# fc.net
KiCad netlist of a schematic drawn in EAGLE
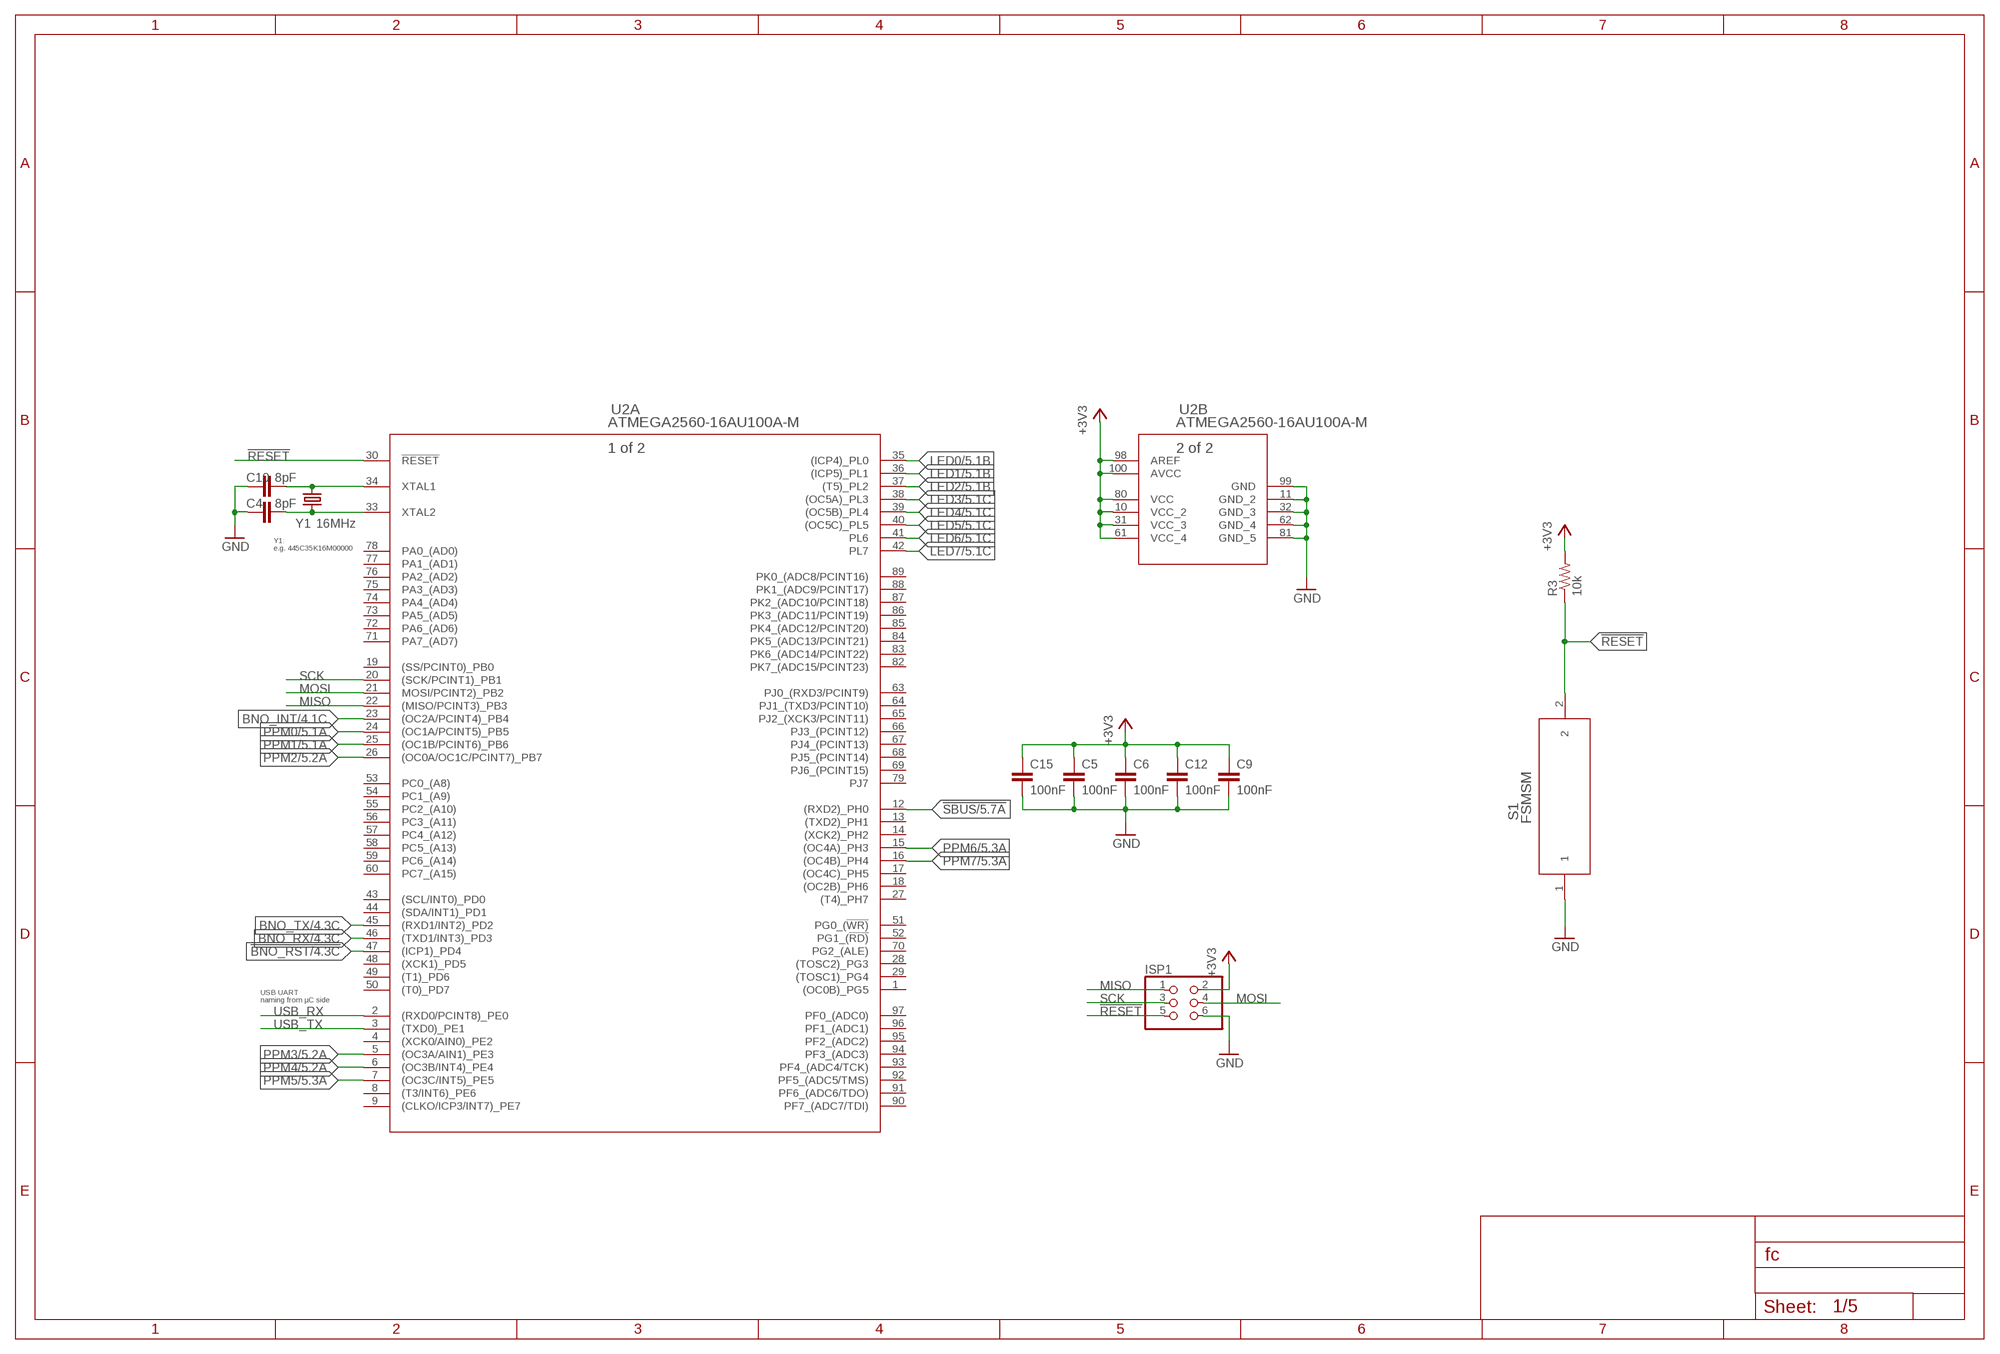
[diagram p0: schematic, sheet 1]
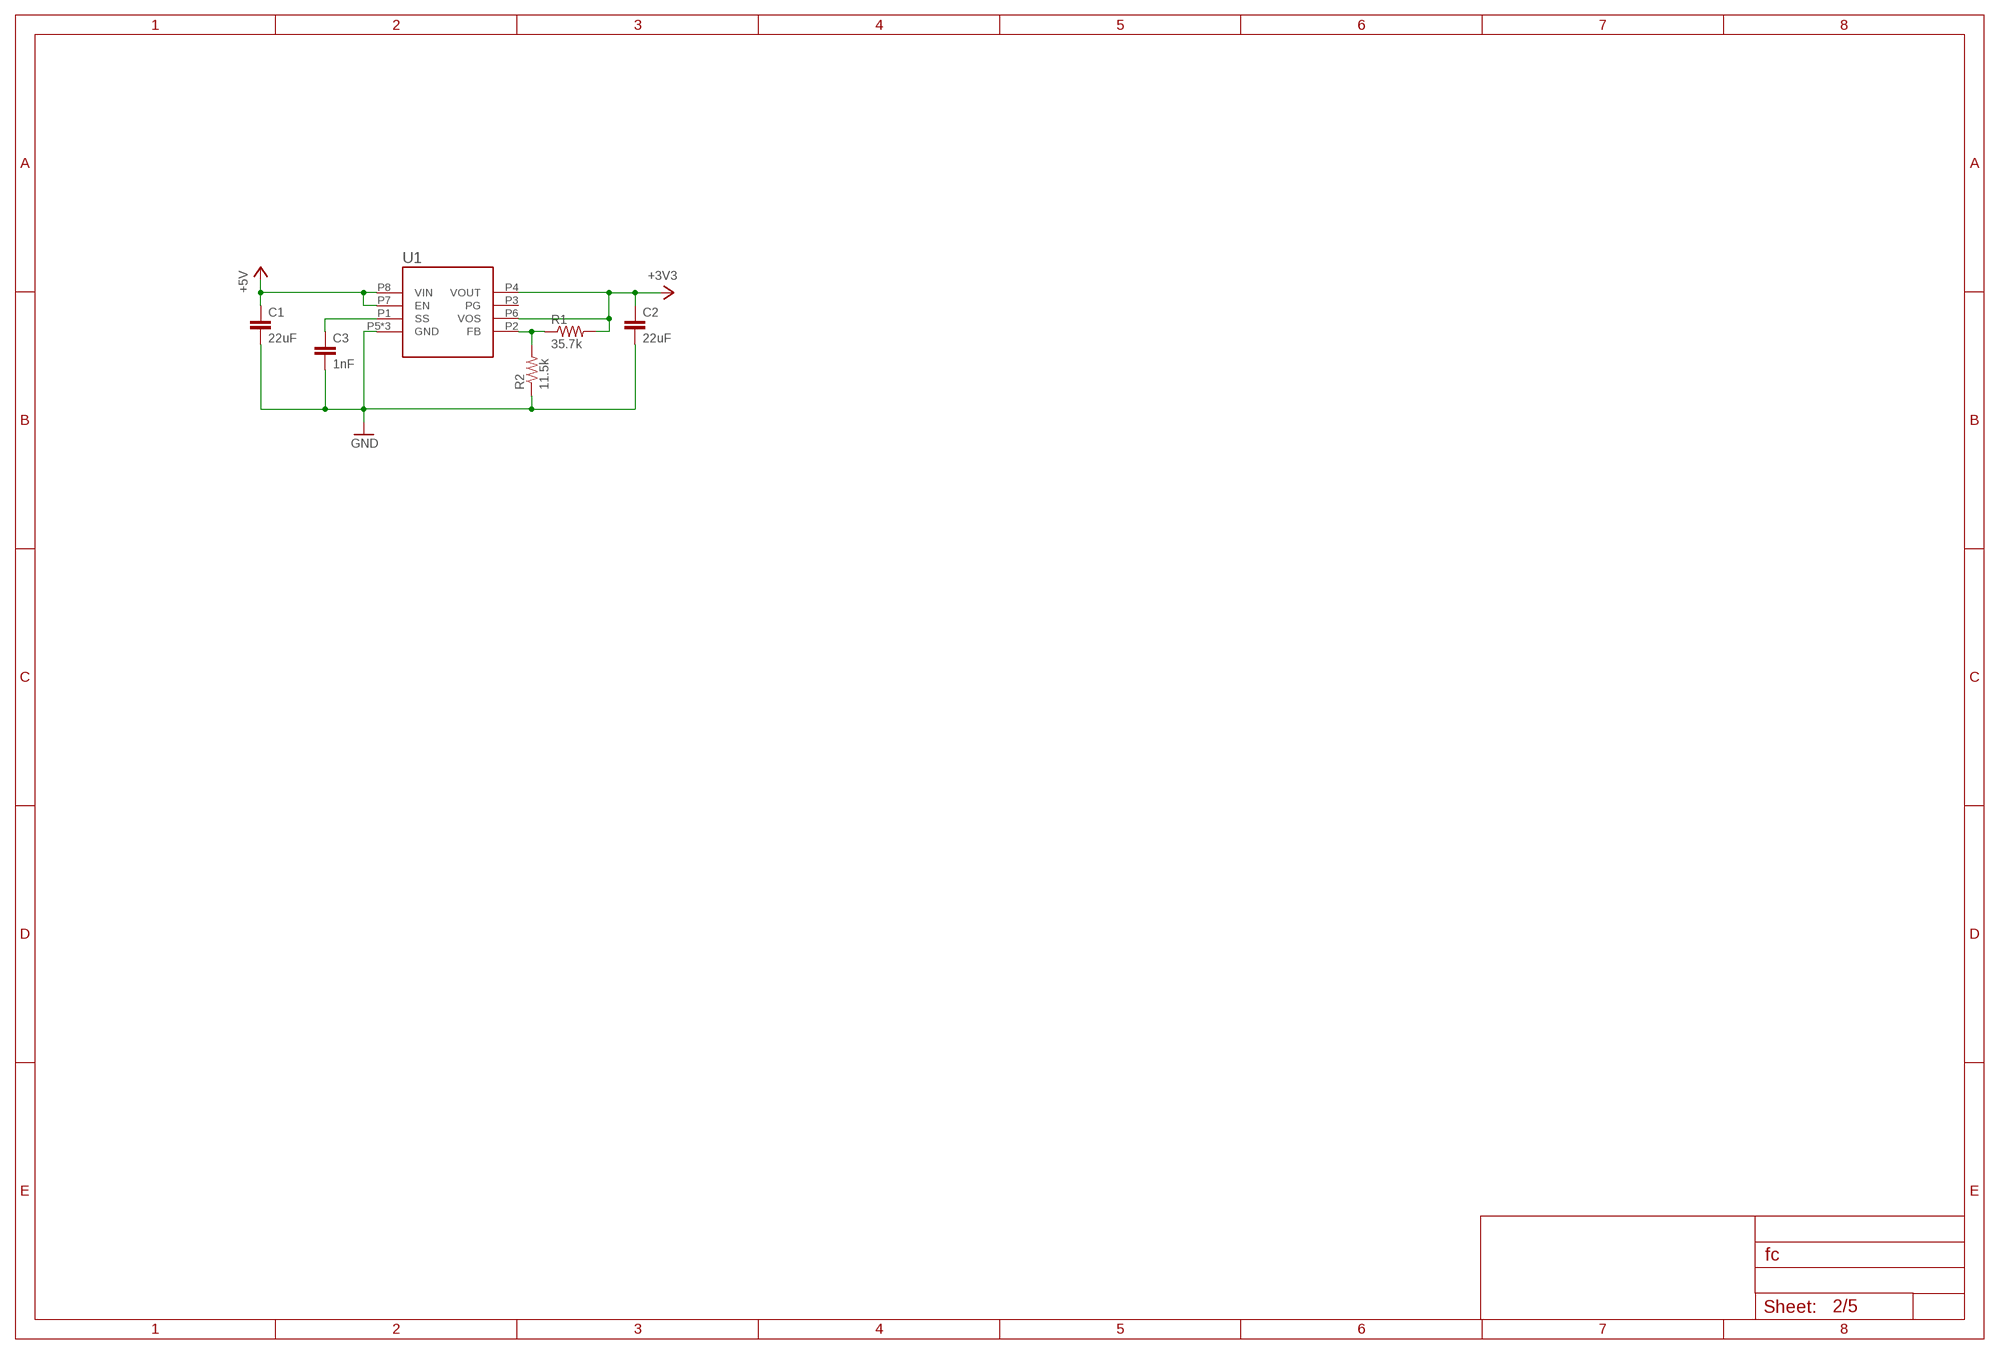
[diagram p1: schematic, sheet 2]
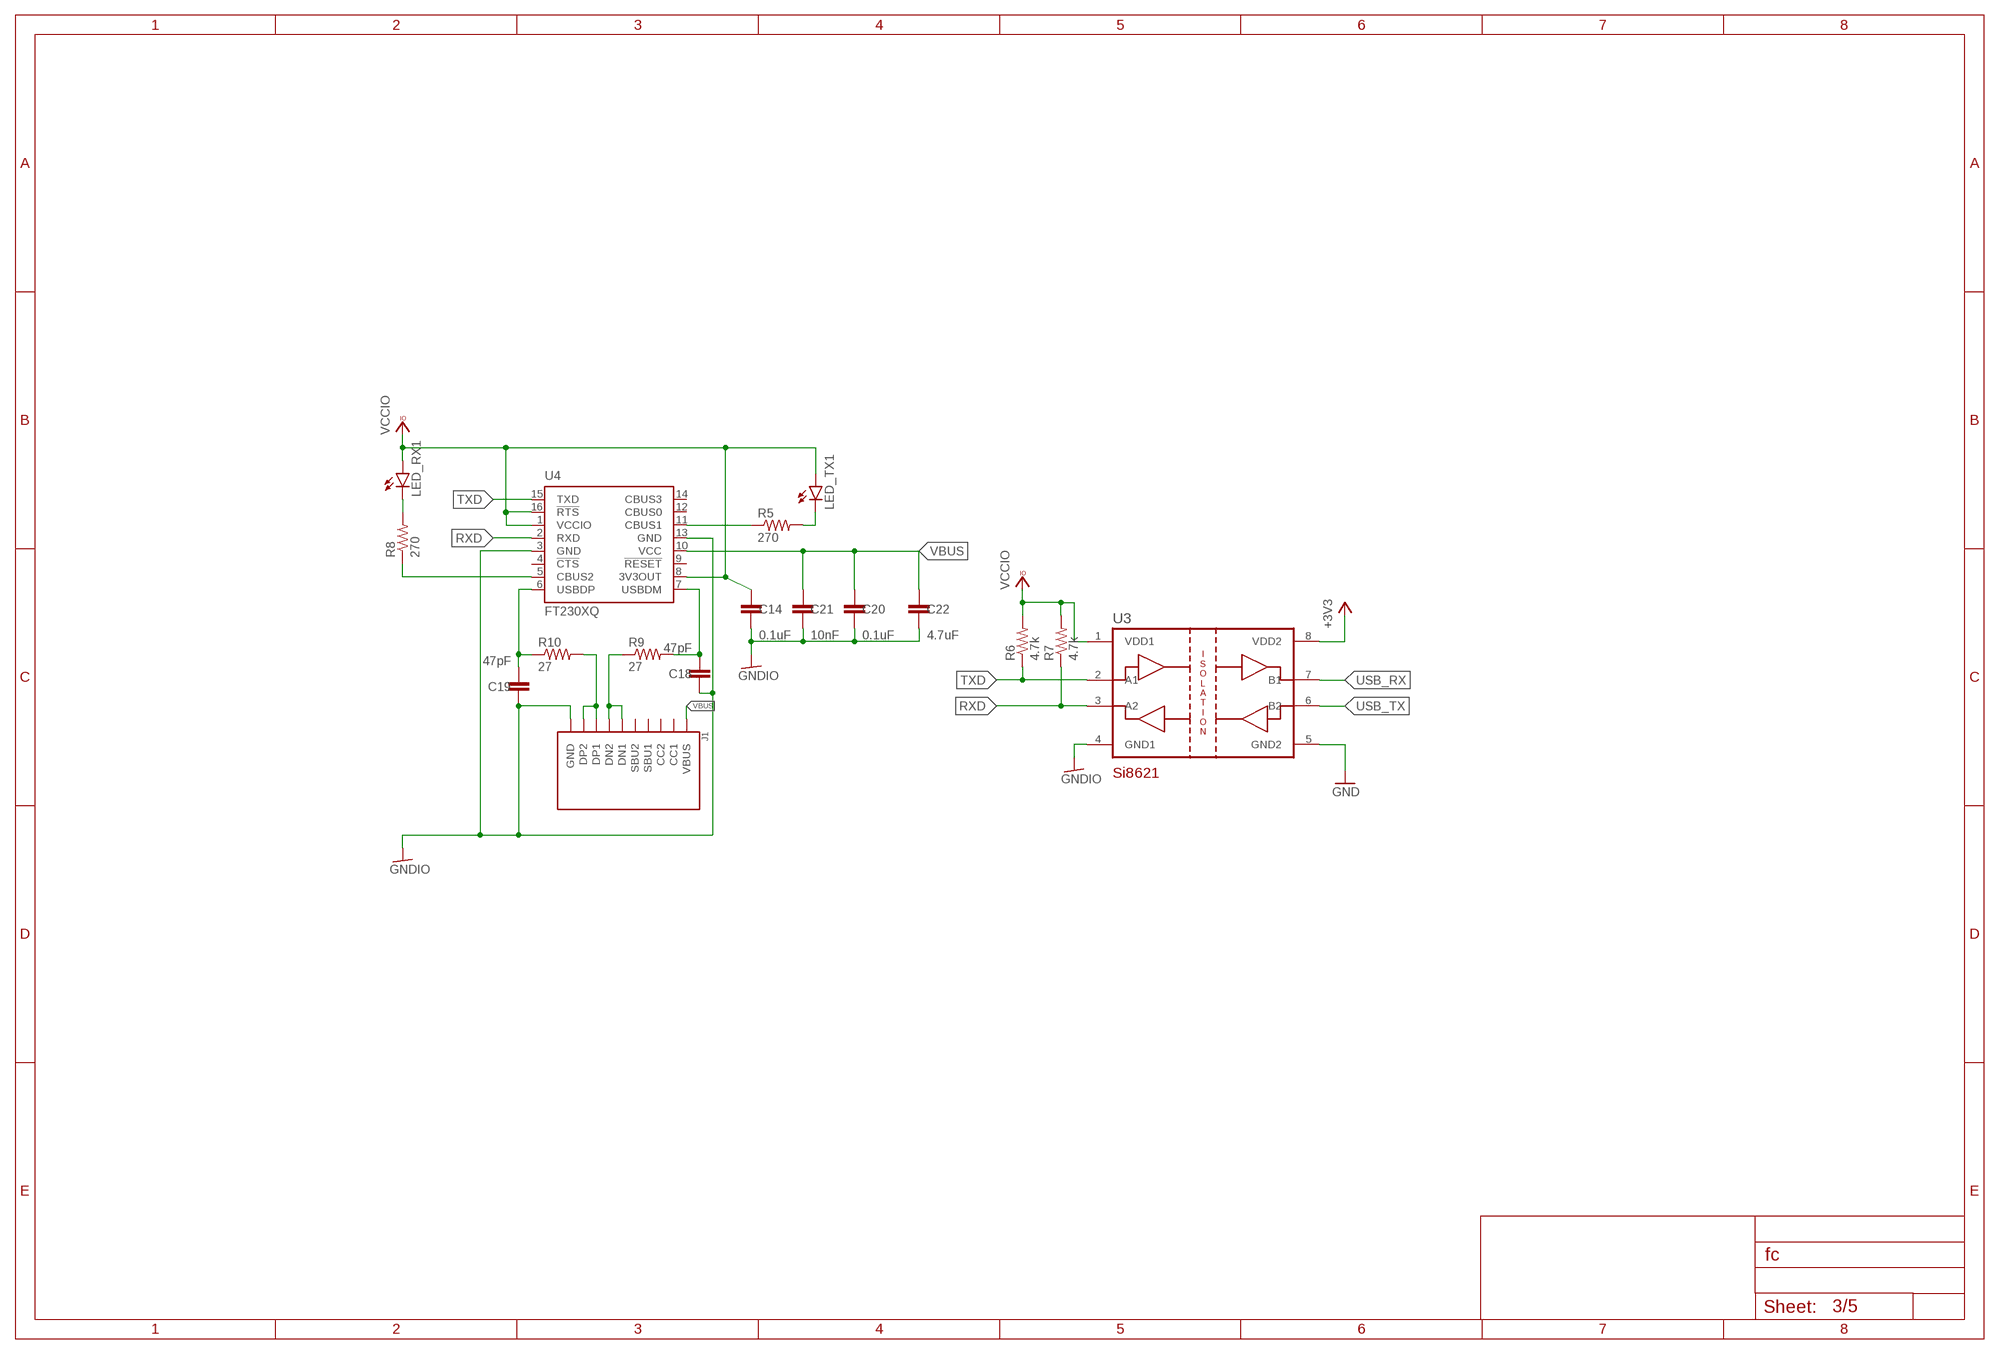
[diagram p2: schematic, sheet 3]
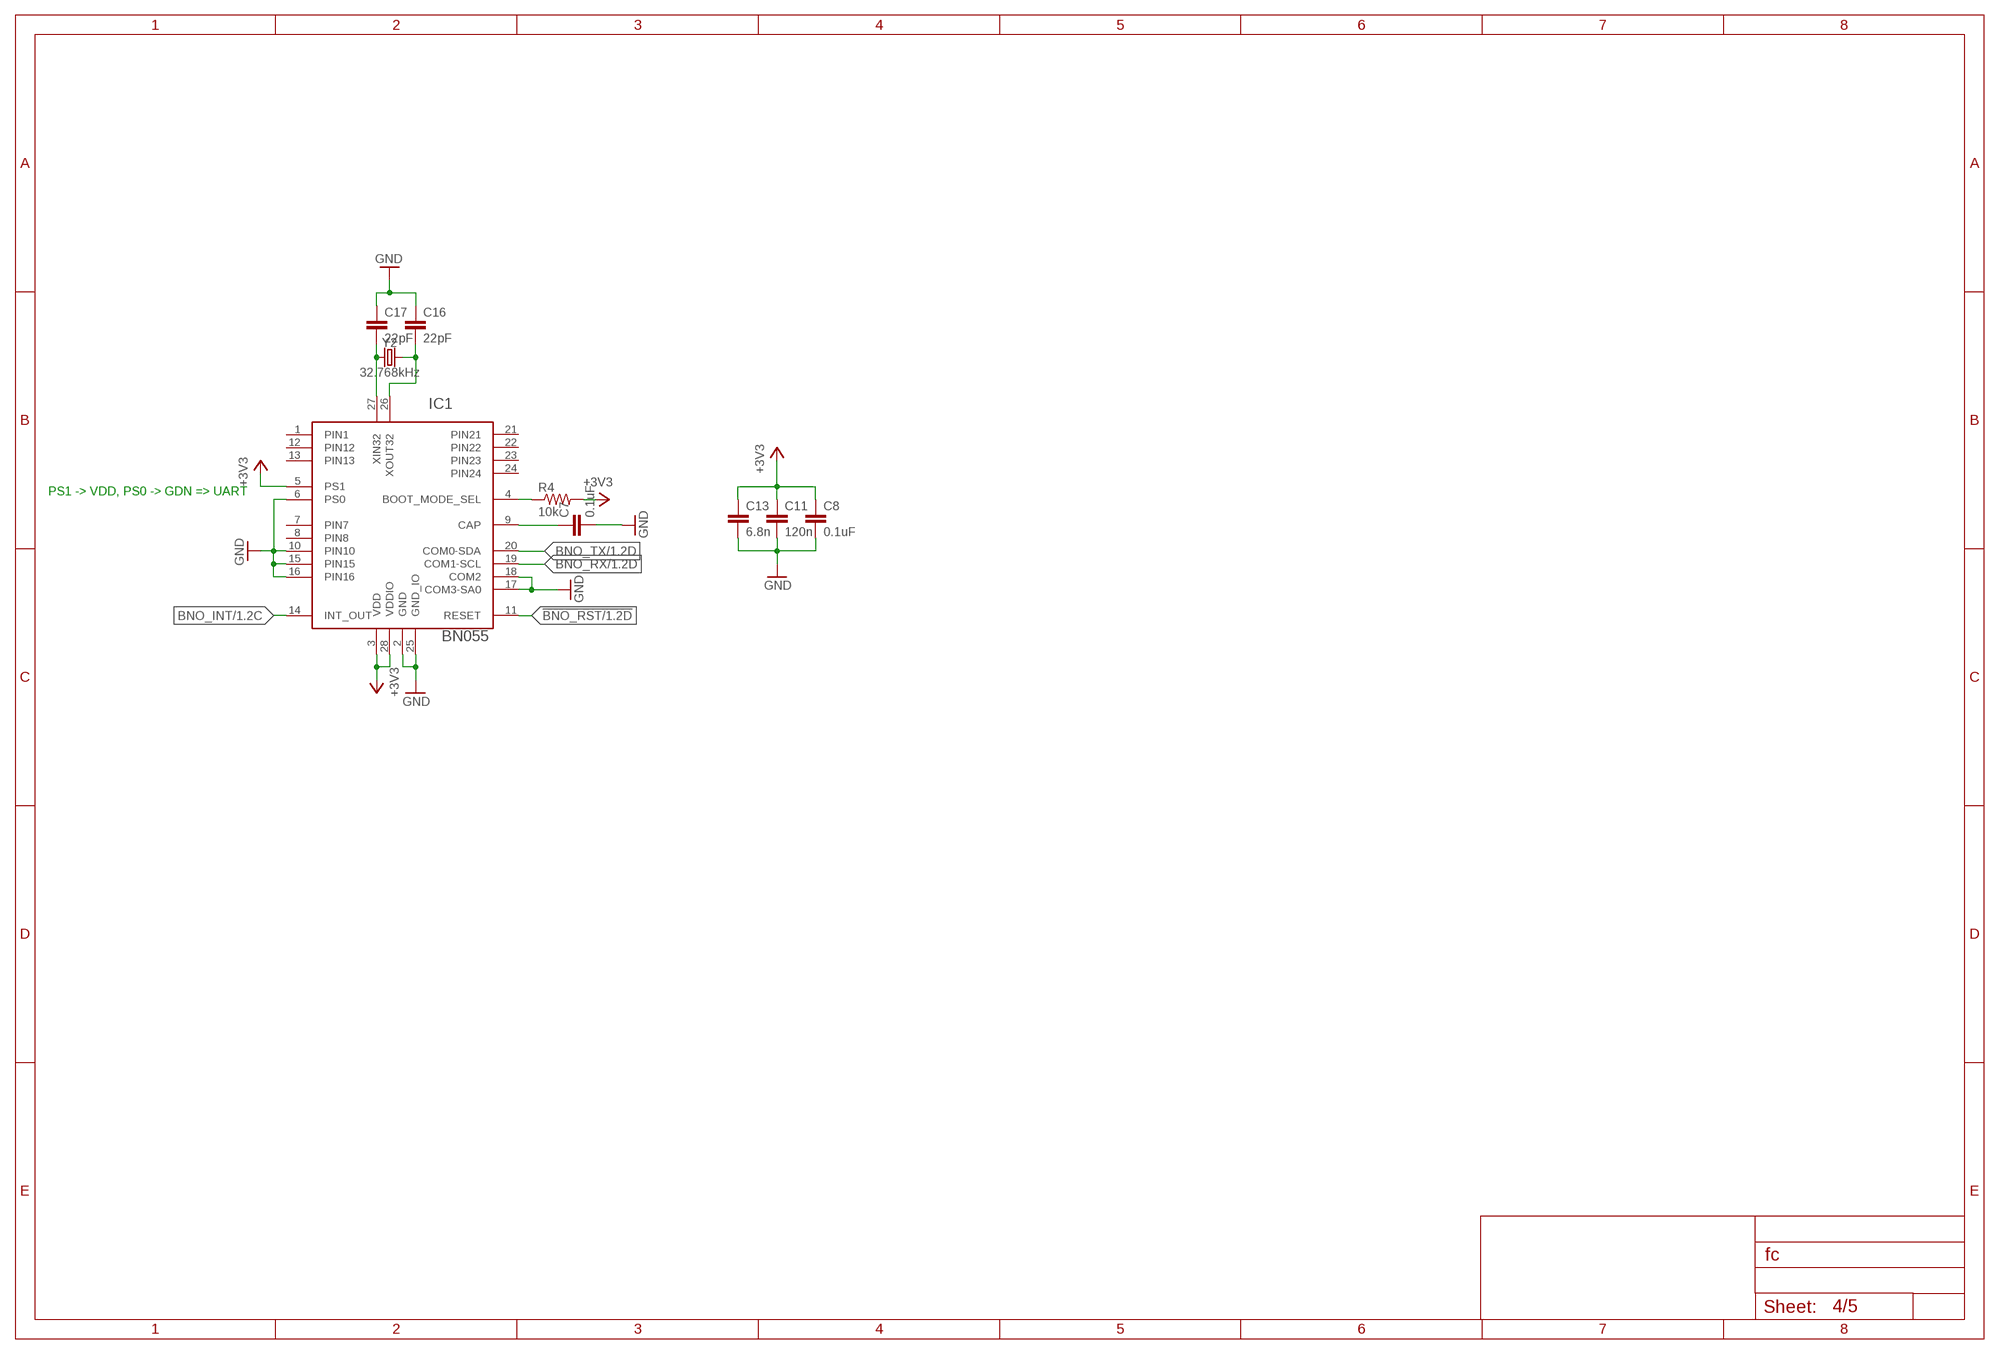
[diagram p3: schematic, sheet 4]
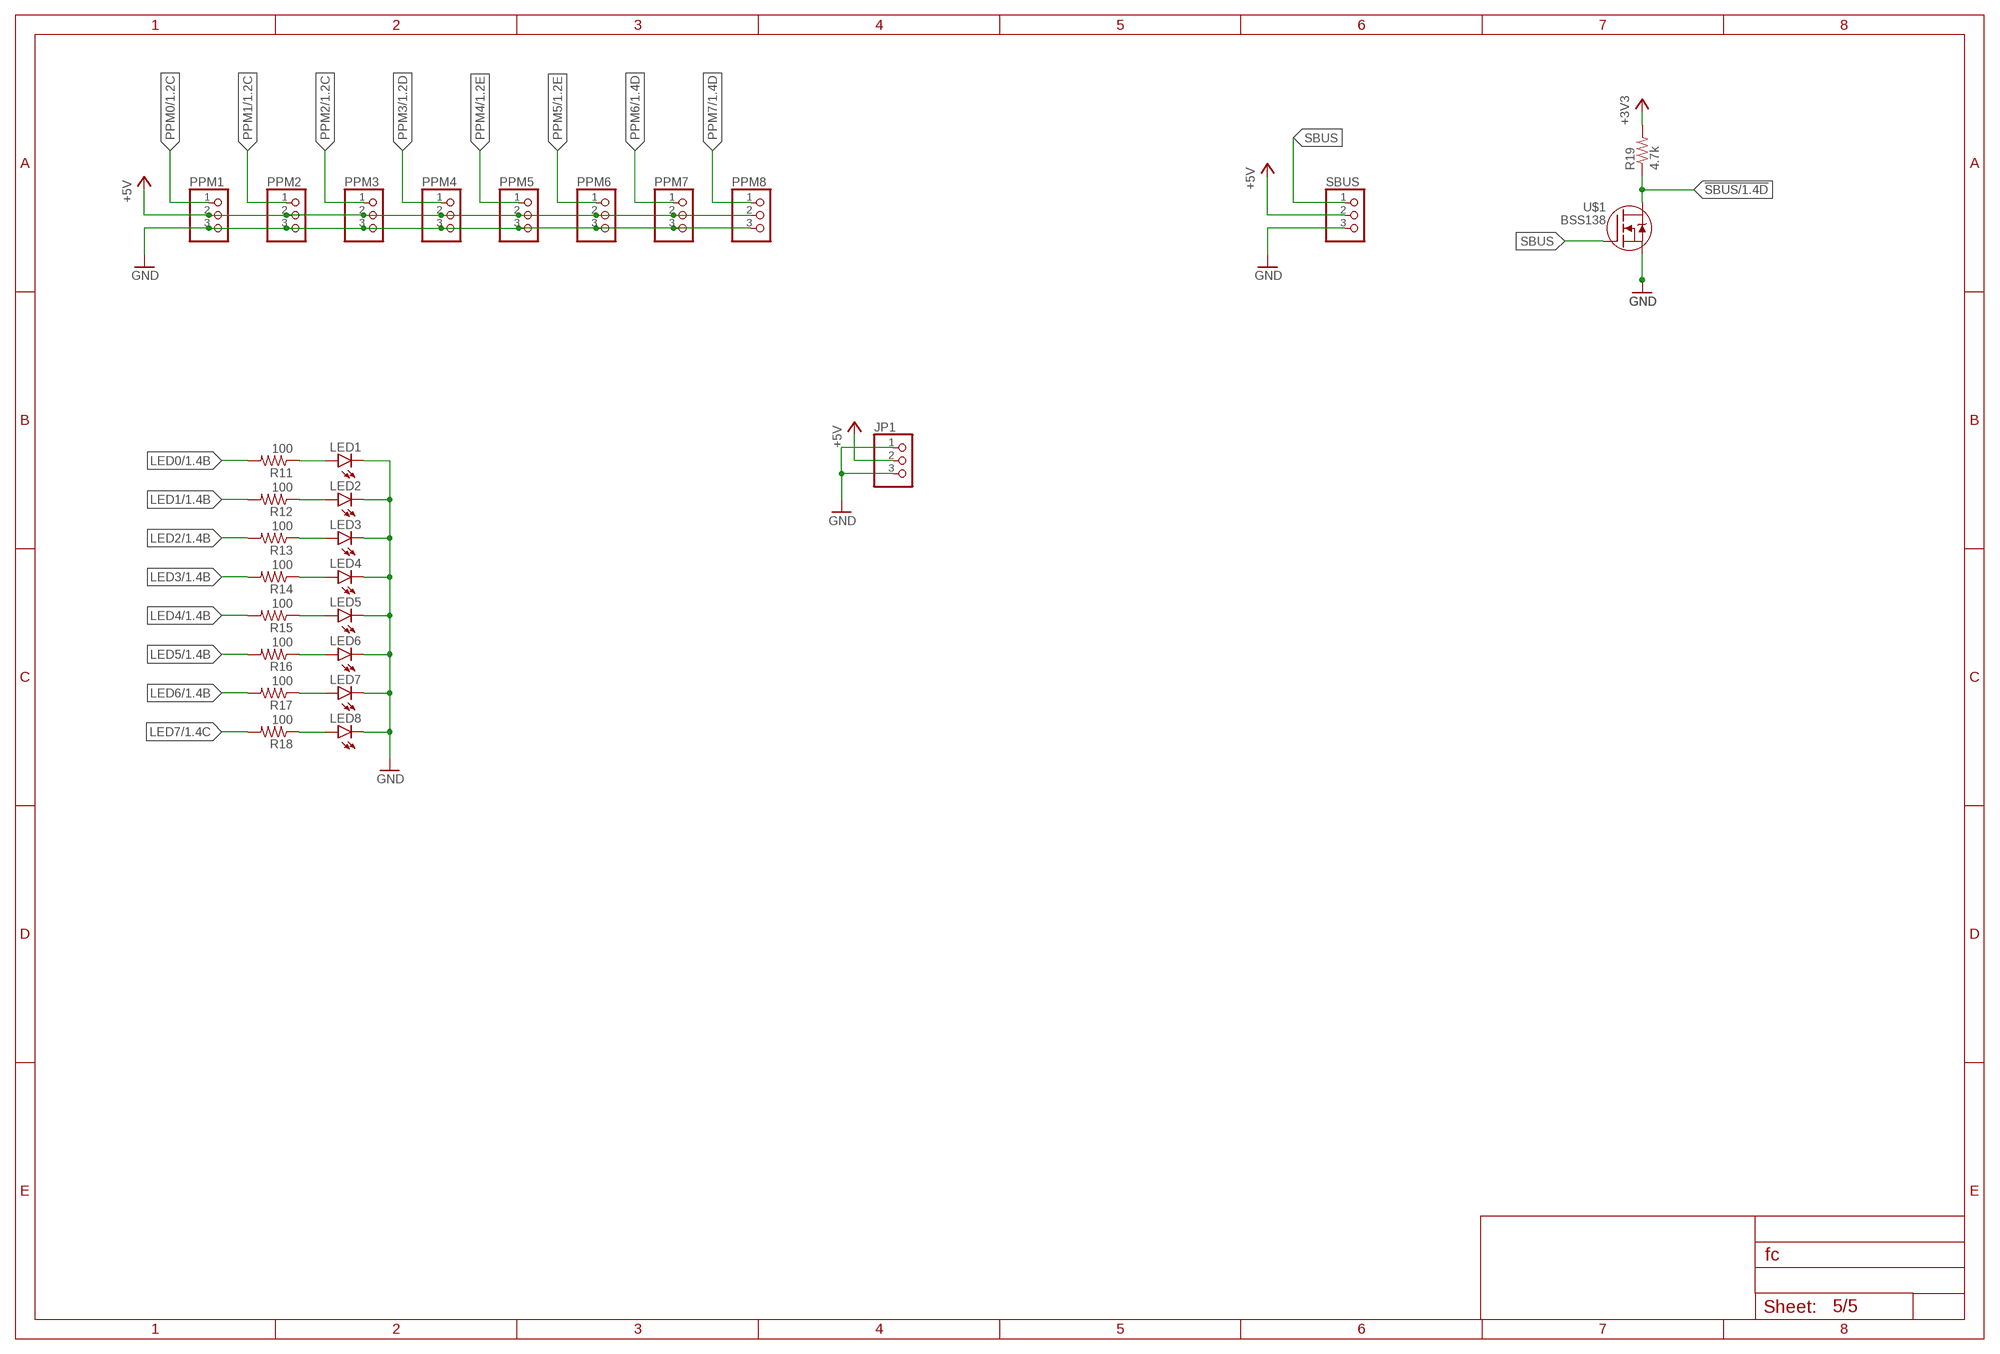
[diagram p4: schematic, sheet 5]

(export (version "E")
  (design (tool "Eeschema 10.0.6"))
  (components
    (comp (ref "C4")
      (value "8pF")
      (footprint "eagle-import:0603")
      (libsource (lib "eagle-import") (part "CAP_GENERIC0603"))
    )
    (comp (ref "C5")
      (value "100nF")
      (footprint "eagle-import:0603")
      (libsource (lib "eagle-import") (part "CAP_GENERIC0603"))
    )
    (comp (ref "C6")
      (value "100nF")
      (footprint "eagle-import:0603")
      (libsource (lib "eagle-import") (part "CAP_GENERIC0603"))
    )
    (comp (ref "C9")
      (value "100nF")
      (footprint "eagle-import:0603")
      (libsource (lib "eagle-import") (part "CAP_GENERIC0603"))
    )
    (comp (ref "C10")
      (value "8pF")
      (footprint "eagle-import:0603")
      (libsource (lib "eagle-import") (part "CAP_GENERIC0603"))
    )
    (comp (ref "C12")
      (value "100nF")
      (footprint "eagle-import:0603")
      (libsource (lib "eagle-import") (part "CAP_GENERIC0603"))
    )
    (comp (ref "C15")
      (value "100nF")
      (footprint "eagle-import:0603")
      (libsource (lib "eagle-import") (part "CAP_GENERIC0603"))
    )
    (comp (ref "ISP1")
      (value "PINHD-2X3")
      (footprint "eagle-import:2X03")
      (libsource (lib "eagle-import") (part "PINHD-2X3"))
    )
    (comp (ref "R3")
      (value "10k")
      (footprint "eagle-import:0603")
      (libsource (lib "eagle-import") (part "RESISTOR0603"))
    )
    (comp (ref "S1")
      (value "FSMSM")
      (footprint "eagle-import:SWITCH_FSMSM")
      (libsource (lib "eagle-import") (part "FSMSM"))
    )
    (comp (ref "U2")
      (value "ATMEGA2560-16AU100A-M")
      (footprint "eagle-import:100A-M")
      (fields (field (name "MANUFACTURER_PART_NUMBER") "ATMEGA256016AU"))
      (libsource (lib "eagle-import") (part "ATMEGA2560-16AU100A-M"))
    )
    (comp (ref "Y1")
      (value "16MHz")
      (footprint "eagle-import:CRYSTAL-SMD-5X3.2-2PAD")
      (libsource (lib "eagle-import") (part "CRYSTALSMD-5X3.2-2PAD"))
    )
    (comp (ref "C14")
      (value "0.1uF")
      (footprint "eagle-import:0603")
      (libsource (lib "eagle-import") (part "0.1UF-0603-25V-5%"))
    )
    (comp (ref "C18")
      (value "47pF")
      (footprint "eagle-import:0603")
      (libsource (lib "eagle-import") (part "47PF-0603-50V-5%"))
    )
    (comp (ref "C19")
      (value "47pF")
      (footprint "eagle-import:0603")
      (libsource (lib "eagle-import") (part "47PF-0603-50V-5%"))
    )
    (comp (ref "C20")
      (value "0.1uF")
      (footprint "eagle-import:0603")
      (libsource (lib "eagle-import") (part "0.1UF-0603-25V-5%"))
    )
    (comp (ref "C21")
      (value "10nF")
      (footprint "eagle-import:0603")
      (libsource (lib "eagle-import") (part "10NF-0603-50V-10%"))
    )
    (comp (ref "C22")
      (value "4.7uF")
      (footprint "eagle-import:0603")
      (libsource (lib "eagle-import") (part "4.7UF0603"))
    )
    (comp (ref "J1")
      (value "USBC")
      (footprint "eagle-import:USBC")
      (libsource (lib "eagle-import") (part "USBC"))
    )
    (comp (ref "LED_RX1")
      (value "LED0603")
      (footprint "eagle-import:LED-0603")
      (libsource (lib "eagle-import") (part "LED0603"))
    )
    (comp (ref "LED_TX1")
      (value "LED0603")
      (footprint "eagle-import:LED-0603")
      (libsource (lib "eagle-import") (part "LED0603"))
    )
    (comp (ref "R5")
      (value "270")
      (footprint "eagle-import:0603")
      (libsource (lib "eagle-import") (part "RESISTOR0603"))
    )
    (comp (ref "R6")
      (value "4.7k")
      (footprint "eagle-import:0603")
      (libsource (lib "eagle-import") (part "4.7KOHM-0603-1/10W-1%"))
    )
    (comp (ref "R7")
      (value "4.7k")
      (footprint "eagle-import:0603")
      (libsource (lib "eagle-import") (part "4.7KOHM-0603-1/10W-1%"))
    )
    (comp (ref "R8")
      (value "270")
      (footprint "eagle-import:0603")
      (libsource (lib "eagle-import") (part "RESISTOR0603"))
    )
    (comp (ref "R9")
      (value "27")
      (footprint "eagle-import:0603")
      (libsource (lib "eagle-import") (part "27OHM-0603-1/10W-1%"))
    )
    (comp (ref "R10")
      (value "27")
      (footprint "eagle-import:0603")
      (libsource (lib "eagle-import") (part "27OHM-0603-1/10W-1%"))
    )
    (comp (ref "U3")
      (value "SI8621AB-B-IS")
      (footprint "eagle-import:SO08")
      (libsource (lib "eagle-import") (part "SI8621AB-B-IS"))
    )
    (comp (ref "U4")
      (value "FT230XQ")
      (footprint "eagle-import:QFN16")
      (libsource (lib "eagle-import") (part "FT230XQ"))
    )
    (comp (ref "C7")
      (value "0.1uF")
      (footprint "eagle-import:0603")
      (libsource (lib "eagle-import") (part "0.1UF-0603-25V-(+80/-20%)"))
    )
    (comp (ref "C8")
      (value "0.1uF")
      (footprint "eagle-import:0603")
      (libsource (lib "eagle-import") (part "0.1UF-0603-25V-(+80/-20%)"))
    )
    (comp (ref "C11")
      (value "120n")
      (footprint "eagle-import:0603")
      (libsource (lib "eagle-import") (part "CAP_GENERIC0603"))
    )
    (comp (ref "C13")
      (value "6.8n")
      (footprint "eagle-import:0603")
      (libsource (lib "eagle-import") (part "CAP_GENERIC0603"))
    )
    (comp (ref "C16")
      (value "22pF")
      (footprint "eagle-import:0603")
      (libsource (lib "eagle-import") (part "22PF-0603-50V-5%"))
    )
    (comp (ref "C17")
      (value "22pF")
      (footprint "eagle-import:0603")
      (libsource (lib "eagle-import") (part "22PF-0603-50V-5%"))
    )
    (comp (ref "IC1")
      (value "BN055")
      (footprint "eagle-import:LGA-28_3.80X5.20_0.5")
      (fields (field (name "PART_NUMBER") "BNO055"))
      (libsource (lib "eagle-import") (part "1658_BNO055"))
    )
    (comp (ref "R4")
      (value "10k")
      (footprint "eagle-import:0603")
      (libsource (lib "eagle-import") (part "RESISTOR0603"))
    )
    (comp (ref "Y2")
      (value "32.768kHz")
      (footprint "eagle-import:CRYSTAL-SMD-3.2X1.5MM")
      (libsource (lib "eagle-import") (part "CRYSTAL-32.768KHZSMD-3.2X1.5"))
    )
    (comp (ref "C1")
      (value "22uF")
      (footprint "eagle-import:0805")
      (libsource (lib "eagle-import") (part "22UF-0805-6.3V-20%"))
    )
    (comp (ref "C2")
      (value "22uF")
      (footprint "eagle-import:0805")
      (libsource (lib "eagle-import") (part "22UF-0805-6.3V-20%"))
    )
    (comp (ref "C3")
      (value "1nF")
      (footprint "eagle-import:0603")
      (libsource (lib "eagle-import") (part "1.0NF/1000PF-0603-50V-10%"))
    )
    (comp (ref "R1")
      (value "35.7k")
      (footprint "eagle-import:0603")
      (libsource (lib "eagle-import") (part "RESISTOR0603"))
    )
    (comp (ref "R2")
      (value "11.5k")
      (footprint "eagle-import:0603")
      (libsource (lib "eagle-import") (part "RESISTOR0603"))
    )
    (comp (ref "U1")
      (value "LMZ21700")
      (footprint "eagle-import:SIL0008E")
      (libsource (lib "eagle-import") (part "LMZ21700"))
    )
    (comp (ref "JP1")
      (value "PINHD-1X3")
      (footprint "eagle-import:1X03")
      (libsource (lib "eagle-import") (part "PINHD-1X3"))
    )
    (comp (ref "LED1")
      (value "LED0603")
      (footprint "eagle-import:LED-0603")
      (libsource (lib "eagle-import") (part "LED0603"))
    )
    (comp (ref "LED2")
      (value "LED0603")
      (footprint "eagle-import:LED-0603")
      (libsource (lib "eagle-import") (part "LED0603"))
    )
    (comp (ref "LED3")
      (value "LED0603")
      (footprint "eagle-import:LED-0603")
      (libsource (lib "eagle-import") (part "LED0603"))
    )
    (comp (ref "LED4")
      (value "LED0603")
      (footprint "eagle-import:LED-0603")
      (libsource (lib "eagle-import") (part "LED0603"))
    )
    (comp (ref "LED5")
      (value "LED0603")
      (footprint "eagle-import:LED-0603")
      (libsource (lib "eagle-import") (part "LED0603"))
    )
    (comp (ref "LED6")
      (value "LED0603")
      (footprint "eagle-import:LED-0603")
      (libsource (lib "eagle-import") (part "LED0603"))
    )
    (comp (ref "LED7")
      (value "LED0603")
      (footprint "eagle-import:LED-0603")
      (libsource (lib "eagle-import") (part "LED0603"))
    )
    (comp (ref "LED8")
      (value "LED0603")
      (footprint "eagle-import:LED-0603")
      (libsource (lib "eagle-import") (part "LED0603"))
    )
    (comp (ref "PPM1")
      (value "PINHD-1X3")
      (footprint "eagle-import:1X03")
      (libsource (lib "eagle-import") (part "PINHD-1X3"))
    )
    (comp (ref "PPM2")
      (value "PINHD-1X3")
      (footprint "eagle-import:1X03")
      (libsource (lib "eagle-import") (part "PINHD-1X3"))
    )
    (comp (ref "PPM3")
      (value "PINHD-1X3")
      (footprint "eagle-import:1X03")
      (libsource (lib "eagle-import") (part "PINHD-1X3"))
    )
    (comp (ref "PPM4")
      (value "PINHD-1X3")
      (footprint "eagle-import:1X03")
      (libsource (lib "eagle-import") (part "PINHD-1X3"))
    )
    (comp (ref "PPM5")
      (value "PINHD-1X3")
      (footprint "eagle-import:1X03")
      (libsource (lib "eagle-import") (part "PINHD-1X3"))
    )
    (comp (ref "PPM6")
      (value "PINHD-1X3")
      (footprint "eagle-import:1X03")
      (libsource (lib "eagle-import") (part "PINHD-1X3"))
    )
    (comp (ref "PPM7")
      (value "PINHD-1X3")
      (footprint "eagle-import:1X03")
      (libsource (lib "eagle-import") (part "PINHD-1X3"))
    )
    (comp (ref "PPM8")
      (value "PINHD-1X3")
      (footprint "eagle-import:1X03")
      (libsource (lib "eagle-import") (part "PINHD-1X3"))
    )
    (comp (ref "R11")
      (value "100")
      (footprint "eagle-import:0603")
      (libsource (lib "eagle-import") (part "RESISTOR0603"))
    )
    (comp (ref "R12")
      (value "100")
      (footprint "eagle-import:0603")
      (libsource (lib "eagle-import") (part "RESISTOR0603"))
    )
    (comp (ref "R13")
      (value "100")
      (footprint "eagle-import:0603")
      (libsource (lib "eagle-import") (part "RESISTOR0603"))
    )
    (comp (ref "R14")
      (value "100")
      (footprint "eagle-import:0603")
      (libsource (lib "eagle-import") (part "RESISTOR0603"))
    )
    (comp (ref "R15")
      (value "100")
      (footprint "eagle-import:0603")
      (libsource (lib "eagle-import") (part "RESISTOR0603"))
    )
    (comp (ref "R16")
      (value "100")
      (footprint "eagle-import:0603")
      (libsource (lib "eagle-import") (part "RESISTOR0603"))
    )
    (comp (ref "R17")
      (value "100")
      (footprint "eagle-import:0603")
      (libsource (lib "eagle-import") (part "RESISTOR0603"))
    )
    (comp (ref "R18")
      (value "100")
      (footprint "eagle-import:0603")
      (libsource (lib "eagle-import") (part "RESISTOR0603"))
    )
    (comp (ref "R19")
      (value "4.7k")
      (footprint "eagle-import:0603")
      (libsource (lib "eagle-import") (part "RESISTOR0603"))
    )
    (comp (ref "SBUS")
      (value "PINHD-1X3")
      (footprint "eagle-import:1X03")
      (libsource (lib "eagle-import") (part "PINHD-1X3"))
    )
    (comp (ref "U$1")
      (value "BSS138")
      (footprint "eagle-import:SOT23")
      (libsource (lib "eagle-import") (part "BSS138"))
    )
  )
  (nets
    (net (code "1") (name "+3V3") (class "Default")
      (node (ref "C11") (pin "1") (pinfunction "1_1") (pintype "passive"))
      (node (ref "C12") (pin "1") (pinfunction "1_1") (pintype "passive"))
      (node (ref "C13") (pin "1") (pinfunction "1_1") (pintype "passive"))
      (node (ref "C15") (pin "1") (pinfunction "1_1") (pintype "passive"))
      (node (ref "C2") (pin "1") (pinfunction "1_1") (pintype "passive"))
      (node (ref "C5") (pin "1") (pinfunction "1_1") (pintype "passive"))
      (node (ref "C6") (pin "1") (pinfunction "1_1") (pintype "passive"))
      (node (ref "C8") (pin "1") (pinfunction "1_1") (pintype "passive"))
      (node (ref "C9") (pin "1") (pinfunction "1_1") (pintype "passive"))
      (node (ref "IC1") (pin "28") (pinfunction "VDDIO_28") (pintype "power_in"))
      (node (ref "IC1") (pin "3") (pinfunction "VDD_3") (pintype "power_in"))
      (node (ref "IC1") (pin "5") (pinfunction "PS1_5") (pintype "input"))
      (node (ref "ISP1") (pin "2") (pinfunction "2_2") (pintype "passive"))
      (node (ref "R1") (pin "2") (pinfunction "2_2") (pintype "passive"))
      (node (ref "R19") (pin "2") (pinfunction "2_2") (pintype "passive"))
      (node (ref "R3") (pin "2") (pinfunction "2_2") (pintype "passive"))
      (node (ref "R4") (pin "2") (pinfunction "2_2") (pintype "passive"))
      (node (ref "U1") (pin "P4") (pinfunction "VOUT_P4") (pintype "bidirectional"))
      (node (ref "U1") (pin "P6") (pinfunction "VOS_P6") (pintype "bidirectional"))
      (node (ref "U2") (pin "10") (pinfunction "VCC_2_10") (pintype "power_in"))
      (node (ref "U2") (pin "100") (pinfunction "AVCC_100") (pintype "power_in"))
      (node (ref "U2") (pin "31") (pinfunction "VCC_3_31") (pintype "power_in"))
      (node (ref "U2") (pin "61") (pinfunction "VCC_4_61") (pintype "power_in"))
      (node (ref "U2") (pin "80") (pinfunction "VCC_80") (pintype "power_in"))
      (node (ref "U2") (pin "98") (pinfunction "AREF_98") (pintype "power_in"))
      (node (ref "U3") (pin "8") (pinfunction "VDD2_8") (pintype "power_in"))
    )
    (net (code "2") (name "+5V") (class "Default")
      (node (ref "C1") (pin "1") (pinfunction "1_1") (pintype "passive"))
      (node (ref "JP1") (pin "2") (pinfunction "2_2") (pintype "passive"))
      (node (ref "PPM1") (pin "2") (pinfunction "2_2") (pintype "passive"))
      (node (ref "PPM2") (pin "2") (pinfunction "2_2") (pintype "passive"))
      (node (ref "PPM3") (pin "2") (pinfunction "2_2") (pintype "passive"))
      (node (ref "PPM4") (pin "2") (pinfunction "2_2") (pintype "passive"))
      (node (ref "PPM5") (pin "2") (pinfunction "2_2") (pintype "passive"))
      (node (ref "PPM6") (pin "2") (pinfunction "2_2") (pintype "passive"))
      (node (ref "PPM7") (pin "2") (pinfunction "2_2") (pintype "passive"))
      (node (ref "PPM8") (pin "2") (pinfunction "2_2") (pintype "passive"))
      (node (ref "SBUS") (pin "2") (pinfunction "2_2") (pintype "passive"))
      (node (ref "U1") (pin "P7") (pinfunction "EN_P7") (pintype "bidirectional"))
      (node (ref "U1") (pin "P8") (pinfunction "VIN_P8") (pintype "bidirectional"))
    )
    (net (code "3") (name "BNO_INT") (class "Default")
      (node (ref "IC1") (pin "14") (pinfunction "INT_OUT_14") (pintype "output"))
      (node (ref "U2") (pin "23") (pinfunction "(OC2A/PCINT4)_PB4_23") (pintype "bidirectional"))
    )
    (net (code "4") (name "BNO_RX") (class "Default")
      (node (ref "IC1") (pin "19") (pinfunction "COM1-SCL_19") (pintype "bidirectional"))
      (node (ref "U2") (pin "46") (pinfunction "(TXD1/INT3)_PD3_46") (pintype "bidirectional"))
    )
    (net (code "5") (name "BNO_TX") (class "Default")
      (node (ref "IC1") (pin "20") (pinfunction "COM0-SDA_20") (pintype "bidirectional"))
      (node (ref "U2") (pin "45") (pinfunction "(RXD1/INT2)_PD2_45") (pintype "bidirectional"))
    )
    (net (code "6") (name "GND") (class "Default")
      (node (ref "C1") (pin "2") (pinfunction "2_2") (pintype "passive"))
      (node (ref "C10") (pin "1") (pinfunction "1_1") (pintype "passive"))
      (node (ref "C11") (pin "2") (pinfunction "2_2") (pintype "passive"))
      (node (ref "C12") (pin "2") (pinfunction "2_2") (pintype "passive"))
      (node (ref "C13") (pin "2") (pinfunction "2_2") (pintype "passive"))
      (node (ref "C15") (pin "2") (pinfunction "2_2") (pintype "passive"))
      (node (ref "C16") (pin "1") (pinfunction "1_1") (pintype "passive"))
      (node (ref "C17") (pin "1") (pinfunction "1_1") (pintype "passive"))
      (node (ref "C2") (pin "2") (pinfunction "2_2") (pintype "passive"))
      (node (ref "C3") (pin "2") (pinfunction "2_2") (pintype "passive"))
      (node (ref "C4") (pin "1") (pinfunction "1_1") (pintype "passive"))
      (node (ref "C5") (pin "2") (pinfunction "2_2") (pintype "passive"))
      (node (ref "C6") (pin "2") (pinfunction "2_2") (pintype "passive"))
      (node (ref "C7") (pin "2") (pinfunction "2_2") (pintype "passive"))
      (node (ref "C8") (pin "2") (pinfunction "2_2") (pintype "passive"))
      (node (ref "C9") (pin "2") (pinfunction "2_2") (pintype "passive"))
      (node (ref "IC1") (pin "10") (pinfunction "PIN10_10") (pintype "passive"))
      (node (ref "IC1") (pin "15") (pinfunction "PIN15_15") (pintype "passive"))
      (node (ref "IC1") (pin "16") (pinfunction "PIN16_16") (pintype "passive"))
      (node (ref "IC1") (pin "17") (pinfunction "COM3-SA0_17") (pintype "bidirectional"))
      (node (ref "IC1") (pin "18") (pinfunction "COM2_18") (pintype "bidirectional"))
      (node (ref "IC1") (pin "2") (pinfunction "GND_2") (pintype "power_in"))
      (node (ref "IC1") (pin "25") (pinfunction "GND_IO_25") (pintype "power_in"))
      (node (ref "IC1") (pin "6") (pinfunction "PS0_6") (pintype "input"))
      (node (ref "ISP1") (pin "6") (pinfunction "6_6") (pintype "passive"))
      (node (ref "JP1") (pin "1") (pinfunction "1_1") (pintype "passive"))
      (node (ref "JP1") (pin "3") (pinfunction "3_3") (pintype "passive"))
      (node (ref "LED1") (pin "C") (pinfunction "C_C") (pintype "passive"))
      (node (ref "LED2") (pin "C") (pinfunction "C_C") (pintype "passive"))
      (node (ref "LED3") (pin "C") (pinfunction "C_C") (pintype "passive"))
      (node (ref "LED4") (pin "C") (pinfunction "C_C") (pintype "passive"))
      (node (ref "LED5") (pin "C") (pinfunction "C_C") (pintype "passive"))
      (node (ref "LED6") (pin "C") (pinfunction "C_C") (pintype "passive"))
      (node (ref "LED7") (pin "C") (pinfunction "C_C") (pintype "passive"))
      (node (ref "LED8") (pin "C") (pinfunction "C_C") (pintype "passive"))
      (node (ref "PPM1") (pin "3") (pinfunction "3_3") (pintype "passive"))
      (node (ref "PPM2") (pin "3") (pinfunction "3_3") (pintype "passive"))
      (node (ref "PPM3") (pin "3") (pinfunction "3_3") (pintype "passive"))
      (node (ref "PPM4") (pin "3") (pinfunction "3_3") (pintype "passive"))
      (node (ref "PPM5") (pin "3") (pinfunction "3_3") (pintype "passive"))
      (node (ref "PPM6") (pin "3") (pinfunction "3_3") (pintype "passive"))
      (node (ref "PPM7") (pin "3") (pinfunction "3_3") (pintype "passive"))
      (node (ref "PPM8") (pin "3") (pinfunction "3_3") (pintype "passive"))
      (node (ref "R2") (pin "1") (pinfunction "1_1") (pintype "passive"))
      (node (ref "S1") (pin "1") (pinfunction "1_1") (pintype "passive"))
      (node (ref "SBUS") (pin "3") (pinfunction "3_3") (pintype "passive"))
      (node (ref "U$1") (pin "2") (pinfunction "S_2") (pintype "bidirectional"))
      (node (ref "U1") (pin "P10") (pinfunction "GND_P10") (pintype "bidirectional"))
      (node (ref "U1") (pin "P5") (pinfunction "GND_P5") (pintype "bidirectional"))
      (node (ref "U1") (pin "P9") (pinfunction "GND_P9") (pintype "bidirectional"))
      (node (ref "U2") (pin "11") (pinfunction "GND_2_11") (pintype "power_in"))
      (node (ref "U2") (pin "32") (pinfunction "GND_3_32") (pintype "power_in"))
      (node (ref "U2") (pin "62") (pinfunction "GND_4_62") (pintype "power_in"))
      (node (ref "U2") (pin "81") (pinfunction "GND_5_81") (pintype "power_in"))
      (node (ref "U2") (pin "99") (pinfunction "GND_99") (pintype "passive"))
      (node (ref "U3") (pin "5") (pinfunction "GND2_5") (pintype "power_in"))
    )
    (net (code "7") (name "GNDIO") (class "Default")
      (node (ref "C14") (pin "2") (pinfunction "2_2") (pintype "passive"))
      (node (ref "C18") (pin "1") (pinfunction "1_1") (pintype "passive"))
      (node (ref "C19") (pin "1") (pinfunction "1_1") (pintype "passive"))
      (node (ref "C20") (pin "2") (pinfunction "2_2") (pintype "passive"))
      (node (ref "C21") (pin "2") (pinfunction "2_2") (pintype "passive"))
      (node (ref "C22") (pin "2") (pinfunction "2_2") (pintype "passive"))
      (node (ref "J1") (pin "A1") (pinfunction "GND_A1") (pintype "bidirectional"))
      (node (ref "J1") (pin "A12") (pinfunction "GND_A12") (pintype "bidirectional"))
      (node (ref "J1") (pin "S1") (pinfunction "GND_S1") (pintype "bidirectional"))
      (node (ref "J1") (pin "S2") (pinfunction "GND_S2") (pintype "bidirectional"))
      (node (ref "J1") (pin "S3") (pinfunction "GND_S3") (pintype "bidirectional"))
      (node (ref "J1") (pin "S4") (pinfunction "GND_S4") (pintype "bidirectional"))
      (node (ref "U3") (pin "4") (pinfunction "GND1_4") (pintype "power_in"))
      (node (ref "U4") (pin "13") (pinfunction "GND_13") (pintype "power_in"))
      (node (ref "U4") (pin "3") (pinfunction "GND_3") (pintype "power_in"))
    )
    (net (code "8") (name "LED0") (class "Default")
      (node (ref "R11") (pin "2") (pinfunction "2_2") (pintype "passive"))
      (node (ref "U2") (pin "35") (pinfunction "(ICP4)_PL0_35") (pintype "bidirectional"))
    )
    (net (code "9") (name "LED1") (class "Default")
      (node (ref "R12") (pin "2") (pinfunction "2_2") (pintype "passive"))
      (node (ref "U2") (pin "36") (pinfunction "(ICP5)_PL1_36") (pintype "bidirectional"))
    )
    (net (code "10") (name "LED2") (class "Default")
      (node (ref "R13") (pin "2") (pinfunction "2_2") (pintype "passive"))
      (node (ref "U2") (pin "37") (pinfunction "(T5)_PL2_37") (pintype "bidirectional"))
    )
    (net (code "11") (name "LED3") (class "Default")
      (node (ref "R14") (pin "2") (pinfunction "2_2") (pintype "passive"))
      (node (ref "U2") (pin "38") (pinfunction "(OC5A)_PL3_38") (pintype "bidirectional"))
    )
    (net (code "12") (name "LED4") (class "Default")
      (node (ref "R15") (pin "2") (pinfunction "2_2") (pintype "passive"))
      (node (ref "U2") (pin "39") (pinfunction "(OC5B)_PL4_39") (pintype "bidirectional"))
    )
    (net (code "13") (name "LED5") (class "Default")
      (node (ref "R16") (pin "2") (pinfunction "2_2") (pintype "passive"))
      (node (ref "U2") (pin "40") (pinfunction "(OC5C)_PL5_40") (pintype "bidirectional"))
    )
    (net (code "14") (name "LED6") (class "Default")
      (node (ref "R17") (pin "2") (pinfunction "2_2") (pintype "passive"))
      (node (ref "U2") (pin "41") (pinfunction "PL6_41") (pintype "bidirectional"))
    )
    (net (code "15") (name "LED7") (class "Default")
      (node (ref "R18") (pin "2") (pinfunction "2_2") (pintype "passive"))
      (node (ref "U2") (pin "42") (pinfunction "PL7_42") (pintype "bidirectional"))
    )
    (net (code "16") (name "MISO") (class "Default")
      (node (ref "ISP1") (pin "1") (pinfunction "1_1") (pintype "passive"))
      (node (ref "U2") (pin "22") (pinfunction "(MISO/PCINT3)_PB3_22") (pintype "bidirectional"))
    )
    (net (code "17") (name "MOSI") (class "Default")
      (node (ref "ISP1") (pin "4") (pinfunction "4_4") (pintype "passive"))
      (node (ref "U2") (pin "21") (pinfunction "MOSI/PCINT2)_PB2_21") (pintype "bidirectional"))
    )
    (net (code "18") (name "Net-(IC1-BOOT_MODE_SEL)") (class "Default")
      (node (ref "IC1") (pin "4") (pinfunction "BOOT_MODE_SEL_4") (pintype "input"))
      (node (ref "R4") (pin "1") (pinfunction "1_1") (pintype "passive"))
    )
    (net (code "19") (name "Net-(IC1-CAP)") (class "Default")
      (node (ref "C7") (pin "1") (pinfunction "1_1") (pintype "passive"))
      (node (ref "IC1") (pin "9") (pinfunction "CAP_9") (pintype "tri_state"))
    )
    (net (code "20") (name "Net-(IC1-XIN32)") (class "Default")
      (node (ref "C17") (pin "2") (pinfunction "2_2") (pintype "passive"))
      (node (ref "IC1") (pin "27") (pinfunction "XIN32_27") (pintype "bidirectional"))
      (node (ref "Y2") (pin "P$1") (pinfunction "1_P$1") (pintype "passive"))
    )
    (net (code "21") (name "Net-(IC1-XOUT32)") (class "Default")
      (node (ref "C16") (pin "2") (pinfunction "2_2") (pintype "passive"))
      (node (ref "IC1") (pin "26") (pinfunction "XOUT32_26") (pintype "output"))
      (node (ref "Y2") (pin "P$2") (pinfunction "2_P$2") (pintype "passive"))
    )
    (net (code "22") (name "Net-(J1-DN1)") (class "Default")
      (node (ref "J1") (pin "A7") (pinfunction "DN1_A7") (pintype "bidirectional"))
      (node (ref "J1") (pin "B7") (pinfunction "DN2_B7") (pintype "bidirectional"))
      (node (ref "R9") (pin "1") (pinfunction "1_1") (pintype "passive"))
    )
    (net (code "23") (name "Net-(J1-DP1)") (class "Default")
      (node (ref "J1") (pin "A6") (pinfunction "DP1_A6") (pintype "bidirectional"))
      (node (ref "J1") (pin "B6") (pinfunction "DP2_B6") (pintype "bidirectional"))
      (node (ref "R10") (pin "2") (pinfunction "2_2") (pintype "passive"))
    )
    (net (code "24") (name "Net-(LED1-PadA)") (class "Default")
      (node (ref "LED1") (pin "A") (pinfunction "A_A") (pintype "passive"))
      (node (ref "R11") (pin "1") (pinfunction "1_1") (pintype "passive"))
    )
    (net (code "25") (name "Net-(LED2-PadA)") (class "Default")
      (node (ref "LED2") (pin "A") (pinfunction "A_A") (pintype "passive"))
      (node (ref "R12") (pin "1") (pinfunction "1_1") (pintype "passive"))
    )
    (net (code "26") (name "Net-(LED3-PadA)") (class "Default")
      (node (ref "LED3") (pin "A") (pinfunction "A_A") (pintype "passive"))
      (node (ref "R13") (pin "1") (pinfunction "1_1") (pintype "passive"))
    )
    (net (code "27") (name "Net-(LED4-PadA)") (class "Default")
      (node (ref "LED4") (pin "A") (pinfunction "A_A") (pintype "passive"))
      (node (ref "R14") (pin "1") (pinfunction "1_1") (pintype "passive"))
    )
    (net (code "28") (name "Net-(LED5-PadA)") (class "Default")
      (node (ref "LED5") (pin "A") (pinfunction "A_A") (pintype "passive"))
      (node (ref "R15") (pin "1") (pinfunction "1_1") (pintype "passive"))
    )
    (net (code "29") (name "Net-(LED6-PadA)") (class "Default")
      (node (ref "LED6") (pin "A") (pinfunction "A_A") (pintype "passive"))
      (node (ref "R16") (pin "1") (pinfunction "1_1") (pintype "passive"))
    )
    (net (code "30") (name "Net-(LED7-PadA)") (class "Default")
      (node (ref "LED7") (pin "A") (pinfunction "A_A") (pintype "passive"))
      (node (ref "R17") (pin "1") (pinfunction "1_1") (pintype "passive"))
    )
    (net (code "31") (name "Net-(LED8-PadA)") (class "Default")
      (node (ref "LED8") (pin "A") (pinfunction "A_A") (pintype "passive"))
      (node (ref "R18") (pin "1") (pinfunction "1_1") (pintype "passive"))
    )
    (net (code "32") (name "Net-(LED_RX1-PadC)") (class "Default")
      (node (ref "LED_RX1") (pin "C") (pinfunction "C_C") (pintype "passive"))
      (node (ref "R8") (pin "2") (pinfunction "2_2") (pintype "passive"))
    )
    (net (code "33") (name "Net-(LED_TX1-PadC)") (class "Default")
      (node (ref "LED_TX1") (pin "C") (pinfunction "C_C") (pintype "passive"))
      (node (ref "R5") (pin "2") (pinfunction "2_2") (pintype "passive"))
    )
    (net (code "34") (name "Net-(U1-FB)") (class "Default")
      (node (ref "R1") (pin "1") (pinfunction "1_1") (pintype "passive"))
      (node (ref "R2") (pin "2") (pinfunction "2_2") (pintype "passive"))
      (node (ref "U1") (pin "P2") (pinfunction "FB_P2") (pintype "bidirectional"))
    )
    (net (code "35") (name "Net-(U1-SS)") (class "Default")
      (node (ref "C3") (pin "1") (pinfunction "1_1") (pintype "passive"))
      (node (ref "U1") (pin "P1") (pinfunction "SS_P1") (pintype "bidirectional"))
    )
    (net (code "36") (name "Net-(U2A-XTAL1)") (class "Default")
      (node (ref "C10") (pin "2") (pinfunction "2_2") (pintype "passive"))
      (node (ref "U2") (pin "34") (pinfunction "XTAL1_34") (pintype "input"))
      (node (ref "Y1") (pin "P$2") (pinfunction "2_P$2") (pintype "passive"))
    )
    (net (code "37") (name "Net-(U2A-XTAL2)") (class "Default")
      (node (ref "C4") (pin "2") (pinfunction "2_2") (pintype "passive"))
      (node (ref "U2") (pin "33") (pinfunction "XTAL2_33") (pintype "output"))
      (node (ref "Y1") (pin "P$1") (pinfunction "1_P$1") (pintype "passive"))
    )
    (net (code "38") (name "Net-(U4-CBUS1)") (class "Default")
      (node (ref "R5") (pin "1") (pinfunction "1_1") (pintype "passive"))
      (node (ref "U4") (pin "11") (pinfunction "CBUS1_11") (pintype "bidirectional"))
    )
    (net (code "39") (name "Net-(U4-CBUS2)") (class "Default")
      (node (ref "R8") (pin "1") (pinfunction "1_1") (pintype "passive"))
      (node (ref "U4") (pin "5") (pinfunction "CBUS2_5") (pintype "bidirectional"))
    )
    (net (code "40") (name "Net-(U4-USBDM)") (class "Default")
      (node (ref "C18") (pin "2") (pinfunction "2_2") (pintype "passive"))
      (node (ref "R9") (pin "2") (pinfunction "2_2") (pintype "passive"))
      (node (ref "U4") (pin "7") (pinfunction "USBDM_7") (pintype "input"))
    )
    (net (code "41") (name "Net-(U4-USBDP)") (class "Default")
      (node (ref "C19") (pin "2") (pinfunction "2_2") (pintype "passive"))
      (node (ref "R10") (pin "1") (pinfunction "1_1") (pintype "passive"))
      (node (ref "U4") (pin "6") (pinfunction "USBDP_6") (pintype "input"))
    )
    (net (code "42") (name "PPM0") (class "Default")
      (node (ref "PPM1") (pin "1") (pinfunction "1_1") (pintype "passive"))
      (node (ref "U2") (pin "24") (pinfunction "(OC1A/PCINT5)_PB5_24") (pintype "bidirectional"))
    )
    (net (code "43") (name "PPM1") (class "Default")
      (node (ref "PPM2") (pin "1") (pinfunction "1_1") (pintype "passive"))
      (node (ref "U2") (pin "25") (pinfunction "(OC1B/PCINT6)_PB6_25") (pintype "bidirectional"))
    )
    (net (code "44") (name "PPM2") (class "Default")
      (node (ref "PPM3") (pin "1") (pinfunction "1_1") (pintype "passive"))
      (node (ref "U2") (pin "26") (pinfunction "(OC0A/OC1C/PCINT7)_PB7_26") (pintype "bidirectional"))
    )
    (net (code "45") (name "PPM3") (class "Default")
      (node (ref "PPM4") (pin "1") (pinfunction "1_1") (pintype "passive"))
      (node (ref "U2") (pin "5") (pinfunction "(OC3A/AIN1)_PE3_5") (pintype "bidirectional"))
    )
    (net (code "46") (name "PPM4") (class "Default")
      (node (ref "PPM5") (pin "1") (pinfunction "1_1") (pintype "passive"))
      (node (ref "U2") (pin "6") (pinfunction "(OC3B/INT4)_PE4_6") (pintype "bidirectional"))
    )
    (net (code "47") (name "PPM5") (class "Default")
      (node (ref "PPM6") (pin "1") (pinfunction "1_1") (pintype "passive"))
      (node (ref "U2") (pin "7") (pinfunction "(OC3C/INT5)_PE5_7") (pintype "bidirectional"))
    )
    (net (code "48") (name "PPM6") (class "Default")
      (node (ref "PPM7") (pin "1") (pinfunction "1_1") (pintype "passive"))
      (node (ref "U2") (pin "15") (pinfunction "(OC4A)_PH3_15") (pintype "bidirectional"))
    )
    (net (code "49") (name "PPM7") (class "Default")
      (node (ref "PPM8") (pin "1") (pinfunction "1_1") (pintype "passive"))
      (node (ref "U2") (pin "16") (pinfunction "(OC4B)_PH4_16") (pintype "bidirectional"))
    )
    (net (code "50") (name "RXD") (class "Default")
      (node (ref "R7") (pin "1") (pinfunction "1_1") (pintype "passive"))
      (node (ref "U3") (pin "3") (pinfunction "A2_3") (pintype "output"))
      (node (ref "U4") (pin "2") (pinfunction "RXD_2") (pintype "input"))
    )
    (net (code "51") (name "SBUS") (class "Default")
      (node (ref "SBUS") (pin "1") (pinfunction "1_1") (pintype "passive"))
      (node (ref "U$1") (pin "1") (pinfunction "G_1") (pintype "bidirectional"))
    )
    (net (code "52") (name "SCK") (class "Default")
      (node (ref "ISP1") (pin "3") (pinfunction "3_3") (pintype "passive"))
      (node (ref "U2") (pin "20") (pinfunction "(SCK/PCINT1)_PB1_20") (pintype "bidirectional"))
    )
    (net (code "53") (name "TXD") (class "Default")
      (node (ref "R6") (pin "1") (pinfunction "1_1") (pintype "passive"))
      (node (ref "U3") (pin "2") (pinfunction "A1_2") (pintype "input"))
      (node (ref "U4") (pin "15") (pinfunction "TXD_15") (pintype "output"))
    )
    (net (code "54") (name "USB_RX") (class "Default")
      (node (ref "U2") (pin "2") (pinfunction "(RXD0/PCINT8)_PE0_2") (pintype "bidirectional"))
      (node (ref "U3") (pin "7") (pinfunction "B1_7") (pintype "output"))
    )
    (net (code "55") (name "USB_TX") (class "Default")
      (node (ref "U2") (pin "3") (pinfunction "(TXD0)_PE1_3") (pintype "bidirectional"))
      (node (ref "U3") (pin "6") (pinfunction "B2_6") (pintype "bidirectional"))
    )
    (net (code "56") (name "VBUS") (class "Default")
      (node (ref "C20") (pin "1") (pinfunction "1_1") (pintype "passive"))
      (node (ref "C21") (pin "1") (pinfunction "1_1") (pintype "passive"))
      (node (ref "C22") (pin "1") (pinfunction "1_1") (pintype "passive"))
      (node (ref "J1") (pin "A4") (pinfunction "VBUS_A4") (pintype "bidirectional"))
      (node (ref "J1") (pin "A9") (pinfunction "VBUS_A9") (pintype "bidirectional"))
      (node (ref "U4") (pin "10") (pinfunction "VCC_10") (pintype "power_in"))
    )
    (net (code "57") (name "VCCIO") (class "Default")
      (node (ref "C14") (pin "1") (pinfunction "1_1") (pintype "passive"))
      (node (ref "LED_RX1") (pin "A") (pinfunction "A_A") (pintype "passive"))
      (node (ref "LED_TX1") (pin "A") (pinfunction "A_A") (pintype "passive"))
      (node (ref "R6") (pin "2") (pinfunction "2_2") (pintype "passive"))
      (node (ref "R7") (pin "2") (pinfunction "2_2") (pintype "passive"))
      (node (ref "U3") (pin "1") (pinfunction "VDD1_1") (pintype "power_in"))
      (node (ref "U4") (pin "1") (pinfunction "VCCIO_1") (pintype "power_in"))
      (node (ref "U4") (pin "16") (pinfunction "~{RTS}_16") (pintype "output"))
      (node (ref "U4") (pin "8") (pinfunction "3V3OUT_8") (pintype "output"))
    )
    (net (code "58") (name "unconnected-(IC1-PIN1-Pad1)") (class "Default")
      (node (ref "IC1") (pin "1") (pinfunction "PIN1_1") (pintype "no_connect"))
    )
    (net (code "59") (name "unconnected-(IC1-PIN7-Pad7)") (class "Default")
      (node (ref "IC1") (pin "7") (pinfunction "PIN7_7") (pintype "tri_state"))
    )
    (net (code "60") (name "unconnected-(IC1-PIN8-Pad8)") (class "Default")
      (node (ref "IC1") (pin "8") (pinfunction "PIN8_8") (pintype "tri_state"))
    )
    (net (code "61") (name "unconnected-(IC1-PIN12-Pad12)") (class "Default")
      (node (ref "IC1") (pin "12") (pinfunction "PIN12_12") (pintype "passive"))
    )
    (net (code "62") (name "unconnected-(IC1-PIN13-Pad13)") (class "Default")
      (node (ref "IC1") (pin "13") (pinfunction "PIN13_13") (pintype "passive"))
    )
    (net (code "63") (name "unconnected-(IC1-PIN21-Pad21)") (class "Default")
      (node (ref "IC1") (pin "21") (pinfunction "PIN21_21") (pintype "passive"))
    )
    (net (code "64") (name "unconnected-(IC1-PIN22-Pad22)") (class "Default")
      (node (ref "IC1") (pin "22") (pinfunction "PIN22_22") (pintype "passive"))
    )
    (net (code "65") (name "unconnected-(IC1-PIN23-Pad23)") (class "Default")
      (node (ref "IC1") (pin "23") (pinfunction "PIN23_23") (pintype "passive"))
    )
    (net (code "66") (name "unconnected-(IC1-PIN24-Pad24)") (class "Default")
      (node (ref "IC1") (pin "24") (pinfunction "PIN24_24") (pintype "passive"))
    )
    (net (code "67") (name "unconnected-(J1-CC1-PadA5)") (class "Default")
      (node (ref "J1") (pin "A5") (pinfunction "CC1_A5") (pintype "bidirectional"))
    )
    (net (code "68") (name "unconnected-(J1-CC2-PadB5)") (class "Default")
      (node (ref "J1") (pin "B5") (pinfunction "CC2_B5") (pintype "bidirectional"))
    )
    (net (code "69") (name "unconnected-(J1-SBU1-PadA8)") (class "Default")
      (node (ref "J1") (pin "A8") (pinfunction "SBU1_A8") (pintype "bidirectional"))
    )
    (net (code "70") (name "unconnected-(J1-SBU2-PadB8)") (class "Default")
      (node (ref "J1") (pin "B8") (pinfunction "SBU2_B8") (pintype "bidirectional"))
    )
    (net (code "71") (name "unconnected-(U1-PG-PadP3)") (class "Default")
      (node (ref "U1") (pin "P3") (pinfunction "PG_P3") (pintype "bidirectional"))
    )
    (net (code "72") (name "unconnected-(U2A-(CLKO{slash}ICP3{slash}INT7)_PE7-Pad9)") (class "Default")
      (node (ref "U2") (pin "9") (pinfunction "(CLKO/ICP3/INT7)_PE7_9") (pintype "bidirectional"))
    )
    (net (code "73") (name "unconnected-(U2A-(OC0B)_PG5-Pad1)") (class "Default")
      (node (ref "U2") (pin "1") (pinfunction "(OC0B)_PG5_1") (pintype "bidirectional"))
    )
    (net (code "74") (name "unconnected-(U2A-(OC2B)_PH6-Pad18)") (class "Default")
      (node (ref "U2") (pin "18") (pinfunction "(OC2B)_PH6_18") (pintype "bidirectional"))
    )
    (net (code "75") (name "unconnected-(U2A-(OC4C)_PH5-Pad17)") (class "Default")
      (node (ref "U2") (pin "17") (pinfunction "(OC4C)_PH5_17") (pintype "bidirectional"))
    )
    (net (code "76") (name "unconnected-(U2A-(SCL{slash}INT0)_PD0-Pad43)") (class "Default")
      (node (ref "U2") (pin "43") (pinfunction "(SCL/INT0)_PD0_43") (pintype "bidirectional"))
    )
    (net (code "77") (name "unconnected-(U2A-(SDA{slash}INT1)_PD1-Pad44)") (class "Default")
      (node (ref "U2") (pin "44") (pinfunction "(SDA/INT1)_PD1_44") (pintype "bidirectional"))
    )
    (net (code "78") (name "unconnected-(U2A-(SS{slash}PCINT0)_PB0-Pad19)") (class "Default")
      (node (ref "U2") (pin "19") (pinfunction "(SS/PCINT0)_PB0_19") (pintype "bidirectional"))
    )
    (net (code "79") (name "unconnected-(U2A-(T0)_PD7-Pad50)") (class "Default")
      (node (ref "U2") (pin "50") (pinfunction "(T0)_PD7_50") (pintype "bidirectional"))
    )
    (net (code "80") (name "unconnected-(U2A-(T1)_PD6-Pad49)") (class "Default")
      (node (ref "U2") (pin "49") (pinfunction "(T1)_PD6_49") (pintype "bidirectional"))
    )
    (net (code "81") (name "unconnected-(U2A-(T3{slash}INT6)_PE6-Pad8)") (class "Default")
      (node (ref "U2") (pin "8") (pinfunction "(T3/INT6)_PE6_8") (pintype "bidirectional"))
    )
    (net (code "82") (name "unconnected-(U2A-(T4)_PH7-Pad27)") (class "Default")
      (node (ref "U2") (pin "27") (pinfunction "(T4)_PH7_27") (pintype "bidirectional"))
    )
    (net (code "83") (name "unconnected-(U2A-(TOSC1)_PG4-Pad29)") (class "Default")
      (node (ref "U2") (pin "29") (pinfunction "(TOSC1)_PG4_29") (pintype "bidirectional"))
    )
    (net (code "84") (name "unconnected-(U2A-(TOSC2)_PG3-Pad28)") (class "Default")
      (node (ref "U2") (pin "28") (pinfunction "(TOSC2)_PG3_28") (pintype "bidirectional"))
    )
    (net (code "85") (name "unconnected-(U2A-(TXD2)_PH1-Pad13)") (class "Default")
      (node (ref "U2") (pin "13") (pinfunction "(TXD2)_PH1_13") (pintype "bidirectional"))
    )
    (net (code "86") (name "unconnected-(U2A-(XCK0{slash}AIN0)_PE2-Pad4)") (class "Default")
      (node (ref "U2") (pin "4") (pinfunction "(XCK0/AIN0)_PE2_4") (pintype "bidirectional"))
    )
    (net (code "87") (name "unconnected-(U2A-(XCK1)_PD5-Pad48)") (class "Default")
      (node (ref "U2") (pin "48") (pinfunction "(XCK1)_PD5_48") (pintype "bidirectional"))
    )
    (net (code "88") (name "unconnected-(U2A-(XCK2)_PH2-Pad14)") (class "Default")
      (node (ref "U2") (pin "14") (pinfunction "(XCK2)_PH2_14") (pintype "bidirectional"))
    )
    (net (code "89") (name "unconnected-(U2A-PA0_(AD0)-Pad78)") (class "Default")
      (node (ref "U2") (pin "78") (pinfunction "PA0_(AD0)_78") (pintype "bidirectional"))
    )
    (net (code "90") (name "unconnected-(U2A-PA1_(AD1)-Pad77)") (class "Default")
      (node (ref "U2") (pin "77") (pinfunction "PA1_(AD1)_77") (pintype "bidirectional"))
    )
    (net (code "91") (name "unconnected-(U2A-PA2_(AD2)-Pad76)") (class "Default")
      (node (ref "U2") (pin "76") (pinfunction "PA2_(AD2)_76") (pintype "bidirectional"))
    )
    (net (code "92") (name "unconnected-(U2A-PA3_(AD3)-Pad75)") (class "Default")
      (node (ref "U2") (pin "75") (pinfunction "PA3_(AD3)_75") (pintype "bidirectional"))
    )
    (net (code "93") (name "unconnected-(U2A-PA4_(AD4)-Pad74)") (class "Default")
      (node (ref "U2") (pin "74") (pinfunction "PA4_(AD4)_74") (pintype "bidirectional"))
    )
    (net (code "94") (name "unconnected-(U2A-PA5_(AD5)-Pad73)") (class "Default")
      (node (ref "U2") (pin "73") (pinfunction "PA5_(AD5)_73") (pintype "bidirectional"))
    )
    (net (code "95") (name "unconnected-(U2A-PA6_(AD6)-Pad72)") (class "Default")
      (node (ref "U2") (pin "72") (pinfunction "PA6_(AD6)_72") (pintype "bidirectional"))
    )
    (net (code "96") (name "unconnected-(U2A-PA7_(AD7)-Pad71)") (class "Default")
      (node (ref "U2") (pin "71") (pinfunction "PA7_(AD7)_71") (pintype "bidirectional"))
    )
    (net (code "97") (name "unconnected-(U2A-PC0_(A8)-Pad53)") (class "Default")
      (node (ref "U2") (pin "53") (pinfunction "PC0_(A8)_53") (pintype "bidirectional"))
    )
    (net (code "98") (name "unconnected-(U2A-PC1_(A9)-Pad54)") (class "Default")
      (node (ref "U2") (pin "54") (pinfunction "PC1_(A9)_54") (pintype "bidirectional"))
    )
    (net (code "99") (name "unconnected-(U2A-PC2_(A10)-Pad55)") (class "Default")
      (node (ref "U2") (pin "55") (pinfunction "PC2_(A10)_55") (pintype "bidirectional"))
    )
    (net (code "100") (name "unconnected-(U2A-PC3_(A11)-Pad56)") (class "Default")
      (node (ref "U2") (pin "56") (pinfunction "PC3_(A11)_56") (pintype "bidirectional"))
    )
    (net (code "101") (name "unconnected-(U2A-PC4_(A12)-Pad57)") (class "Default")
      (node (ref "U2") (pin "57") (pinfunction "PC4_(A12)_57") (pintype "bidirectional"))
    )
    (net (code "102") (name "unconnected-(U2A-PC5_(A13)-Pad58)") (class "Default")
      (node (ref "U2") (pin "58") (pinfunction "PC5_(A13)_58") (pintype "bidirectional"))
    )
    (net (code "103") (name "unconnected-(U2A-PC6_(A14)-Pad59)") (class "Default")
      (node (ref "U2") (pin "59") (pinfunction "PC6_(A14)_59") (pintype "bidirectional"))
    )
    (net (code "104") (name "unconnected-(U2A-PC7_(A15)-Pad60)") (class "Default")
      (node (ref "U2") (pin "60") (pinfunction "PC7_(A15)_60") (pintype "bidirectional"))
    )
    (net (code "105") (name "unconnected-(U2A-PF0_(ADC0)-Pad97)") (class "Default")
      (node (ref "U2") (pin "97") (pinfunction "PF0_(ADC0)_97") (pintype "bidirectional"))
    )
    (net (code "106") (name "unconnected-(U2A-PF1_(ADC1)-Pad96)") (class "Default")
      (node (ref "U2") (pin "96") (pinfunction "PF1_(ADC1)_96") (pintype "bidirectional"))
    )
    (net (code "107") (name "unconnected-(U2A-PF2_(ADC2)-Pad95)") (class "Default")
      (node (ref "U2") (pin "95") (pinfunction "PF2_(ADC2)_95") (pintype "bidirectional"))
    )
    (net (code "108") (name "unconnected-(U2A-PF3_(ADC3)-Pad94)") (class "Default")
      (node (ref "U2") (pin "94") (pinfunction "PF3_(ADC3)_94") (pintype "bidirectional"))
    )
    (net (code "109") (name "unconnected-(U2A-PF4_(ADC4{slash}TCK)-Pad93)") (class "Default")
      (node (ref "U2") (pin "93") (pinfunction "PF4_(ADC4/TCK)_93") (pintype "bidirectional"))
    )
    (net (code "110") (name "unconnected-(U2A-PF5_(ADC5{slash}TMS)-Pad92)") (class "Default")
      (node (ref "U2") (pin "92") (pinfunction "PF5_(ADC5/TMS)_92") (pintype "bidirectional"))
    )
    (net (code "111") (name "unconnected-(U2A-PF6_(ADC6{slash}TDO)-Pad91)") (class "Default")
      (node (ref "U2") (pin "91") (pinfunction "PF6_(ADC6/TDO)_91") (pintype "bidirectional"))
    )
    (net (code "112") (name "unconnected-(U2A-PF7_(ADC7{slash}TDI)-Pad90)") (class "Default")
      (node (ref "U2") (pin "90") (pinfunction "PF7_(ADC7/TDI)_90") (pintype "bidirectional"))
    )
    (net (code "113") (name "unconnected-(U2A-PG0_(~{WR})-Pad51)") (class "Default")
      (node (ref "U2") (pin "51") (pinfunction "PG0_(~{WR})_51") (pintype "bidirectional"))
    )
    (net (code "114") (name "unconnected-(U2A-PG1_(~{RD})-Pad52)") (class "Default")
      (node (ref "U2") (pin "52") (pinfunction "PG1_(~{RD})_52") (pintype "bidirectional"))
    )
    (net (code "115") (name "unconnected-(U2A-PG2_(ALE)-Pad70)") (class "Default")
      (node (ref "U2") (pin "70") (pinfunction "PG2_(ALE)_70") (pintype "bidirectional"))
    )
    (net (code "116") (name "unconnected-(U2A-PJ0_(RXD3{slash}PCINT9)-Pad63)") (class "Default")
      (node (ref "U2") (pin "63") (pinfunction "PJ0_(RXD3/PCINT9)_63") (pintype "bidirectional"))
    )
    (net (code "117") (name "unconnected-(U2A-PJ1_(TXD3{slash}PCINT10)-Pad64)") (class "Default")
      (node (ref "U2") (pin "64") (pinfunction "PJ1_(TXD3/PCINT10)_64") (pintype "bidirectional"))
    )
    (net (code "118") (name "unconnected-(U2A-PJ2_(XCK3{slash}PCINT11)-Pad65)") (class "Default")
      (node (ref "U2") (pin "65") (pinfunction "PJ2_(XCK3/PCINT11)_65") (pintype "bidirectional"))
    )
    (net (code "119") (name "unconnected-(U2A-PJ3_(PCINT12)-Pad66)") (class "Default")
      (node (ref "U2") (pin "66") (pinfunction "PJ3_(PCINT12)_66") (pintype "bidirectional"))
    )
    (net (code "120") (name "unconnected-(U2A-PJ4_(PCINT13)-Pad67)") (class "Default")
      (node (ref "U2") (pin "67") (pinfunction "PJ4_(PCINT13)_67") (pintype "bidirectional"))
    )
    (net (code "121") (name "unconnected-(U2A-PJ5_(PCINT14)-Pad68)") (class "Default")
      (node (ref "U2") (pin "68") (pinfunction "PJ5_(PCINT14)_68") (pintype "bidirectional"))
    )
    (net (code "122") (name "unconnected-(U2A-PJ6_(PCINT15)-Pad69)") (class "Default")
      (node (ref "U2") (pin "69") (pinfunction "PJ6_(PCINT15)_69") (pintype "bidirectional"))
    )
    (net (code "123") (name "unconnected-(U2A-PJ7-Pad79)") (class "Default")
      (node (ref "U2") (pin "79") (pinfunction "PJ7_79") (pintype "bidirectional"))
    )
    (net (code "124") (name "unconnected-(U2A-PK0_(ADC8{slash}PCINT16)-Pad89)") (class "Default")
      (node (ref "U2") (pin "89") (pinfunction "PK0_(ADC8/PCINT16)_89") (pintype "bidirectional"))
    )
    (net (code "125") (name "unconnected-(U2A-PK1_(ADC9{slash}PCINT17)-Pad88)") (class "Default")
      (node (ref "U2") (pin "88") (pinfunction "PK1_(ADC9/PCINT17)_88") (pintype "bidirectional"))
    )
    (net (code "126") (name "unconnected-(U2A-PK2_(ADC10{slash}PCINT18)-Pad87)") (class "Default")
      (node (ref "U2") (pin "87") (pinfunction "PK2_(ADC10/PCINT18)_87") (pintype "bidirectional"))
    )
    (net (code "127") (name "unconnected-(U2A-PK3_(ADC11{slash}PCINT19)-Pad86)") (class "Default")
      (node (ref "U2") (pin "86") (pinfunction "PK3_(ADC11/PCINT19)_86") (pintype "bidirectional"))
    )
    (net (code "128") (name "unconnected-(U2A-PK4_(ADC12{slash}PCINT20)-Pad85)") (class "Default")
      (node (ref "U2") (pin "85") (pinfunction "PK4_(ADC12/PCINT20)_85") (pintype "bidirectional"))
    )
    (net (code "129") (name "unconnected-(U2A-PK5_(ADC13{slash}PCINT21)-Pad84)") (class "Default")
      (node (ref "U2") (pin "84") (pinfunction "PK5_(ADC13/PCINT21)_84") (pintype "bidirectional"))
    )
    (net (code "130") (name "unconnected-(U2A-PK6_(ADC14{slash}PCINT22)-Pad83)") (class "Default")
      (node (ref "U2") (pin "83") (pinfunction "PK6_(ADC14/PCINT22)_83") (pintype "bidirectional"))
    )
    (net (code "131") (name "unconnected-(U2A-PK7_(ADC15{slash}PCINT23)-Pad82)") (class "Default")
      (node (ref "U2") (pin "82") (pinfunction "PK7_(ADC15/PCINT23)_82") (pintype "bidirectional"))
    )
    (net (code "132") (name "unconnected-(U4-CBUS0-Pad12)") (class "Default")
      (node (ref "U4") (pin "12") (pinfunction "CBUS0_12") (pintype "bidirectional"))
    )
    (net (code "133") (name "unconnected-(U4-CBUS3-Pad14)") (class "Default")
      (node (ref "U4") (pin "14") (pinfunction "CBUS3_14") (pintype "bidirectional"))
    )
    (net (code "134") (name "unconnected-(U4-~{CTS}-Pad4)") (class "Default")
      (node (ref "U4") (pin "4") (pinfunction "~{CTS}_4") (pintype "input"))
    )
    (net (code "135") (name "unconnected-(U4-~{RESET}-Pad9)") (class "Default")
      (node (ref "U4") (pin "9") (pinfunction "~{RESET}_9") (pintype "input"))
    )
    (net (code "136") (name "~{BNO_RST}") (class "Default")
      (node (ref "IC1") (pin "11") (pinfunction "RESET_11") (pintype "input"))
      (node (ref "U2") (pin "47") (pinfunction "(ICP1)_PD4_47") (pintype "bidirectional"))
    )
    (net (code "137") (name "~{RESET}") (class "Default")
      (node (ref "ISP1") (pin "5") (pinfunction "5_5") (pintype "passive"))
      (node (ref "R3") (pin "1") (pinfunction "1_1") (pintype "passive"))
      (node (ref "S1") (pin "2") (pinfunction "2_2") (pintype "passive"))
      (node (ref "U2") (pin "30") (pinfunction "~{RESET}_30") (pintype "input"))
    )
    (net (code "138") (name "~{SBUS}") (class "Default")
      (node (ref "R19") (pin "1") (pinfunction "1_1") (pintype "passive"))
      (node (ref "U$1") (pin "3") (pinfunction "D_3") (pintype "bidirectional"))
      (node (ref "U2") (pin "12") (pinfunction "(RXD2)_PH0_12") (pintype "bidirectional"))
    )
  )
)
